# mapleCUL_small_31.net
KiCad netlist of a schematic drawn in EAGLE
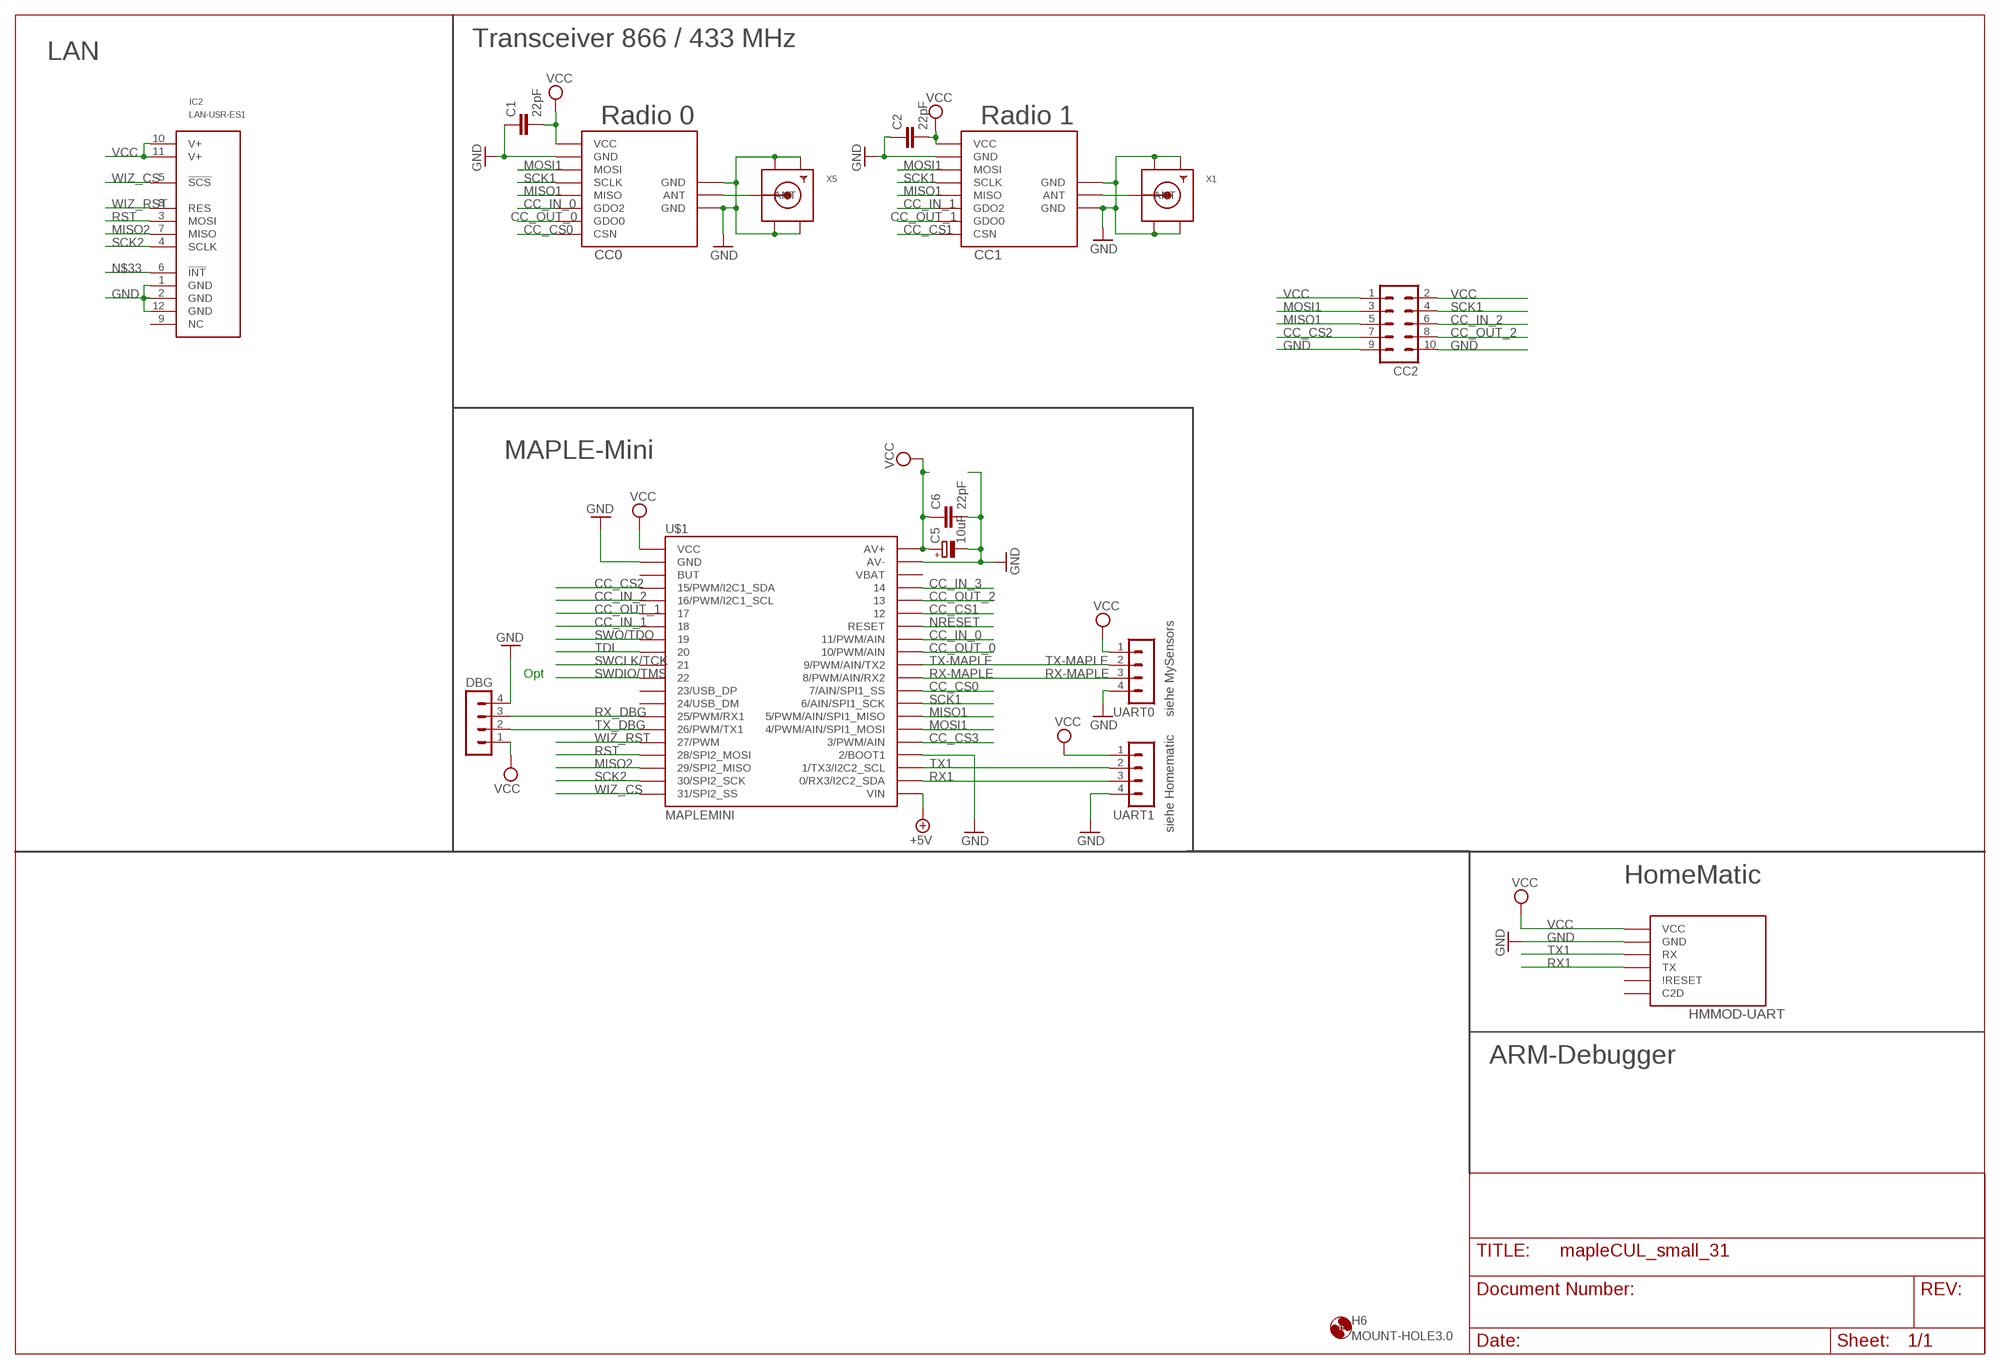
[diagram p0: schematic, sheet 1]

(export (version "E")
  (design (tool "Eeschema 10.0.6"))
  (components
    (comp (ref "C1")
      (value "22pF")
      (footprint "eagle-import:C0805")
      (libsource (lib "eagle-import") (part "C-EUC0805"))
    )
    (comp (ref "C2")
      (value "22pF")
      (footprint "eagle-import:C0805")
      (libsource (lib "eagle-import") (part "C-EUC0805"))
    )
    (comp (ref "C5")
      (value "10uF")
      (footprint "eagle-import:R_2012-12W")
      (libsource (lib "eagle-import") (part "CPOL-EUR/2012-12W"))
    )
    (comp (ref "C6")
      (value "22pF")
      (footprint "eagle-import:C0805")
      (libsource (lib "eagle-import") (part "C-EUC0805"))
    )
    (comp (ref "CC0")
      (value "CC1101")
      (footprint "eagle-import:CC1101_MODULE1_SMD")
      (libsource (lib "eagle-import") (part "CC1101_MODULE1SMD"))
    )
    (comp (ref "CC1")
      (value "CC1101_MODULE1SMD")
      (footprint "eagle-import:CC1101_MODULE1_SMD")
      (libsource (lib "eagle-import") (part "CC1101_MODULE1SMD"))
    )
    (comp (ref "CC2")
      (value "MA05-2")
      (footprint "eagle-import:MA05-2")
      (libsource (lib "eagle-import") (part "MA05-2"))
    )
    (comp (ref "DBG")
      (value "MA04-1")
      (footprint "eagle-import:MA04-1")
      (libsource (lib "eagle-import") (part "MA04-1"))
    )
    (comp (ref "H6")
      (value "MOUNT-HOLE3.0")
      (footprint "eagle-import:3,0")
      (libsource (lib "eagle-import") (part "MOUNT-HOLE3.0"))
    )
    (comp (ref "HMMOD-UART")
      (value "HM-MOD-UARTDIL")
      (footprint "eagle-import:HM-MOD-UART-DIL")
      (libsource (lib "eagle-import") (part "HM-MOD-UARTDIL"))
    )
    (comp (ref "IC2")
      (value "LAN-USR-ES1")
      (footprint "eagle-import:USR-ES1")
      (libsource (lib "eagle-import") (part "LAN-USR-ES1"))
    )
    (comp (ref "U$1")
      (value "MAPLEMINI")
      (footprint "eagle-import:20-DIP")
      (libsource (lib "eagle-import") (part "MAPLEMINI"))
    )
    (comp (ref "UART0")
      (value "MA04-1")
      (footprint "eagle-import:MA04-1")
      (libsource (lib "eagle-import") (part "MA04-1"))
    )
    (comp (ref "UART1")
      (value "MA04-1")
      (footprint "eagle-import:MA04-1")
      (libsource (lib "eagle-import") (part "MA04-1"))
    )
    (comp (ref "X1")
      (value "SMACONNECTOR_EDGE_UFL")
      (footprint "eagle-import:SMA_EDGELAUNCH_UFL")
      (libsource (lib "eagle-import") (part "SMACONNECTOR_EDGE_UFL"))
    )
    (comp (ref "X5")
      (value "SMACONNECTOR_EDGE_UFL")
      (footprint "eagle-import:SMA_EDGELAUNCH_UFL")
      (libsource (lib "eagle-import") (part "SMACONNECTOR_EDGE_UFL"))
    )
  )
  (nets
    (net (code "1") (name "+5V") (class "Default")
      (node (ref "U$1") (pin "21") (pinfunction "VIN_21") (pintype "bidirectional"))
    )
    (net (code "2") (name "/CC_CS0") (class "Default")
      (node (ref "CC0") (pin "CSN") (pinfunction "CSN_CSN") (pintype "bidirectional"))
      (node (ref "U$1") (pin "29") (pinfunction "7/AIN/SPI1_SS_29") (pintype "bidirectional"))
    )
    (net (code "3") (name "/CC_CS1") (class "Default")
      (node (ref "CC1") (pin "CSN") (pinfunction "CSN_CSN") (pintype "bidirectional"))
      (node (ref "U$1") (pin "35") (pinfunction "12_35") (pintype "bidirectional"))
    )
    (net (code "4") (name "/CC_CS2") (class "Default")
      (node (ref "CC2") (pin "7") (pinfunction "7_7") (pintype "passive"))
      (node (ref "U$1") (pin "4") (pinfunction "15/PWM/I2C1_SDA_4") (pintype "bidirectional"))
    )
    (net (code "5") (name "/CC_CS3") (class "Default")
      (node (ref "U$1") (pin "25") (pinfunction "3/PWM/AIN_25") (pintype "bidirectional"))
    )
    (net (code "6") (name "/CC_IN_0") (class "Default")
      (node (ref "CC0") (pin "GDO2") (pinfunction "GDO2_GDO2") (pintype "bidirectional"))
      (node (ref "U$1") (pin "33") (pinfunction "11/PWM/AIN_33") (pintype "bidirectional"))
    )
    (net (code "7") (name "/CC_IN_1") (class "Default")
      (node (ref "CC1") (pin "GDO2") (pinfunction "GDO2_GDO2") (pintype "bidirectional"))
      (node (ref "U$1") (pin "7") (pinfunction "18_7") (pintype "bidirectional"))
    )
    (net (code "8") (name "/CC_IN_2") (class "Default")
      (node (ref "CC2") (pin "6") (pinfunction "6_6") (pintype "passive"))
      (node (ref "U$1") (pin "5") (pinfunction "16/PWM/I2C1_SCL_5") (pintype "bidirectional"))
    )
    (net (code "9") (name "/CC_IN_3") (class "Default")
      (node (ref "U$1") (pin "37") (pinfunction "14_37") (pintype "bidirectional"))
    )
    (net (code "10") (name "/CC_OUT_0") (class "Default")
      (node (ref "CC0") (pin "GDO0") (pinfunction "GDO0_GDO0") (pintype "bidirectional"))
      (node (ref "U$1") (pin "32") (pinfunction "10/PWM/AIN_32") (pintype "bidirectional"))
    )
    (net (code "11") (name "/CC_OUT_1") (class "Default")
      (node (ref "CC1") (pin "GDO0") (pinfunction "GDO0_GDO0") (pintype "bidirectional"))
      (node (ref "U$1") (pin "6") (pinfunction "17_6") (pintype "bidirectional"))
    )
    (net (code "12") (name "/CC_OUT_2") (class "Default")
      (node (ref "CC2") (pin "8") (pinfunction "8_8") (pintype "passive"))
      (node (ref "U$1") (pin "36") (pinfunction "13_36") (pintype "bidirectional"))
    )
    (net (code "13") (name "/MISO1") (class "Default")
      (node (ref "CC0") (pin "MISO") (pinfunction "MISO_MISO") (pintype "bidirectional"))
      (node (ref "CC1") (pin "MISO") (pinfunction "MISO_MISO") (pintype "bidirectional"))
      (node (ref "CC2") (pin "5") (pinfunction "5_5") (pintype "passive"))
      (node (ref "U$1") (pin "27") (pinfunction "5/PWM/AIN/SPI1_MISO_27") (pintype "bidirectional"))
    )
    (net (code "14") (name "/MISO2") (class "Default")
      (node (ref "IC2") (pin "7") (pinfunction "MISO_7") (pintype "bidirectional"))
      (node (ref "U$1") (pin "18") (pinfunction "29/SPI2_MISO_18") (pintype "bidirectional"))
    )
    (net (code "15") (name "/MOSI1") (class "Default")
      (node (ref "CC0") (pin "MOSI") (pinfunction "MOSI_MOSI") (pintype "bidirectional"))
      (node (ref "CC1") (pin "MOSI") (pinfunction "MOSI_MOSI") (pintype "bidirectional"))
      (node (ref "CC2") (pin "3") (pinfunction "3_3") (pintype "passive"))
      (node (ref "U$1") (pin "26") (pinfunction "4/PWM/AIN/SPI1_MOSI_26") (pintype "bidirectional"))
    )
    (net (code "16") (name "/N$33") (class "Default")
      (node (ref "IC2") (pin "6") (pinfunction "~{INT}_6") (pintype "output"))
    )
    (net (code "17") (name "/NRESET") (class "Default")
      (node (ref "U$1") (pin "34") (pinfunction "RESET_34") (pintype "bidirectional"))
    )
    (net (code "18") (name "/RST") (class "Default")
      (node (ref "IC2") (pin "3") (pinfunction "MOSI_3") (pintype "bidirectional"))
      (node (ref "U$1") (pin "17") (pinfunction "28/SPI2_MOSI_17") (pintype "bidirectional"))
    )
    (net (code "19") (name "/RX-MAPLE") (class "Default")
      (node (ref "U$1") (pin "30") (pinfunction "8/PWM/AIN/RX2_30") (pintype "bidirectional"))
      (node (ref "UART0") (pin "3") (pinfunction "3_3") (pintype "passive"))
    )
    (net (code "20") (name "/RX1") (class "Default")
      (node (ref "HMMOD-UART") (pin "5") (pinfunction "TX_5") (pintype "bidirectional"))
      (node (ref "U$1") (pin "22") (pinfunction "0/RX3/I2C2_SDA_22") (pintype "bidirectional"))
      (node (ref "UART1") (pin "3") (pinfunction "3_3") (pintype "passive"))
    )
    (net (code "21") (name "/RX_DBG") (class "Default")
      (node (ref "DBG") (pin "3") (pinfunction "3_3") (pintype "passive"))
      (node (ref "U$1") (pin "14") (pinfunction "25/PWM/RX1_14") (pintype "bidirectional"))
    )
    (net (code "22") (name "/SCK1") (class "Default")
      (node (ref "CC0") (pin "SCLK") (pinfunction "SCLK_SCLK") (pintype "bidirectional"))
      (node (ref "CC1") (pin "SCLK") (pinfunction "SCLK_SCLK") (pintype "bidirectional"))
      (node (ref "CC2") (pin "4") (pinfunction "4_4") (pintype "passive"))
      (node (ref "U$1") (pin "28") (pinfunction "6/AIN/SPI1_SCK_28") (pintype "bidirectional"))
    )
    (net (code "23") (name "/SCK2") (class "Default")
      (node (ref "IC2") (pin "4") (pinfunction "SCLK_4") (pintype "input"))
      (node (ref "U$1") (pin "19") (pinfunction "30/SPI2_SCK_19") (pintype "bidirectional"))
    )
    (net (code "24") (name "/SWCLK{slash}TCK") (class "Default")
      (node (ref "U$1") (pin "10") (pinfunction "21_10") (pintype "bidirectional"))
    )
    (net (code "25") (name "/SWDIO{slash}TMS") (class "Default")
      (node (ref "U$1") (pin "11") (pinfunction "22_11") (pintype "bidirectional"))
    )
    (net (code "26") (name "/SWO{slash}TDO") (class "Default")
      (node (ref "U$1") (pin "8") (pinfunction "19_8") (pintype "bidirectional"))
    )
    (net (code "27") (name "/TDI") (class "Default")
      (node (ref "U$1") (pin "9") (pinfunction "20_9") (pintype "bidirectional"))
    )
    (net (code "28") (name "/TX-MAPLE") (class "Default")
      (node (ref "U$1") (pin "31") (pinfunction "9/PWM/AIN/TX2_31") (pintype "bidirectional"))
      (node (ref "UART0") (pin "2") (pinfunction "2_2") (pintype "passive"))
    )
    (net (code "29") (name "/TX1") (class "Default")
      (node (ref "HMMOD-UART") (pin "6") (pinfunction "RX_6") (pintype "bidirectional"))
      (node (ref "U$1") (pin "23") (pinfunction "1/TX3/I2C2_SCL_23") (pintype "bidirectional"))
      (node (ref "UART1") (pin "2") (pinfunction "2_2") (pintype "passive"))
    )
    (net (code "30") (name "/TX_DBG") (class "Default")
      (node (ref "DBG") (pin "2") (pinfunction "2_2") (pintype "passive"))
      (node (ref "U$1") (pin "15") (pinfunction "26/PWM/TX1_15") (pintype "bidirectional"))
    )
    (net (code "31") (name "/WIZ_CS") (class "Default")
      (node (ref "IC2") (pin "5") (pinfunction "~{SCS}_5") (pintype "input"))
      (node (ref "U$1") (pin "20") (pinfunction "31/SPI2_SS_20") (pintype "bidirectional"))
    )
    (net (code "32") (name "/WIZ_RST") (class "Default")
      (node (ref "IC2") (pin "8") (pinfunction "RES_8") (pintype "input"))
      (node (ref "U$1") (pin "16") (pinfunction "27/PWM_16") (pintype "bidirectional"))
    )
    (net (code "33") (name "GND") (class "Default")
      (node (ref "C1") (pin "1") (pinfunction "1_1") (pintype "passive"))
      (node (ref "C2") (pin "1") (pinfunction "1_1") (pintype "passive"))
      (node (ref "C5") (pin "-") (pinfunction "-_-") (pintype "passive"))
      (node (ref "C6") (pin "2") (pinfunction "2_2") (pintype "passive"))
      (node (ref "CC0") (pin "GND@0") (pinfunction "GND_GND@0") (pintype "power_in"))
      (node (ref "CC0") (pin "GND@1") (pinfunction "GND_GND@1") (pintype "power_in"))
      (node (ref "CC0") (pin "GND@2") (pinfunction "GND_GND@2") (pintype "power_in"))
      (node (ref "CC1") (pin "GND@0") (pinfunction "GND_GND@0") (pintype "power_in"))
      (node (ref "CC1") (pin "GND@1") (pinfunction "GND_GND@1") (pintype "power_in"))
      (node (ref "CC1") (pin "GND@2") (pinfunction "GND_GND@2") (pintype "power_in"))
      (node (ref "CC2") (pin "10") (pinfunction "10_10") (pintype "passive"))
      (node (ref "CC2") (pin "9") (pinfunction "9_9") (pintype "passive"))
      (node (ref "DBG") (pin "4") (pinfunction "4_4") (pintype "passive"))
      (node (ref "HMMOD-UART") (pin "2") (pinfunction "GND_2") (pintype "power_in"))
      (node (ref "IC2") (pin "1") (pinfunction "GND_1") (pintype "power_in"))
      (node (ref "IC2") (pin "12") (pinfunction "GND_12") (pintype "power_in"))
      (node (ref "IC2") (pin "2") (pinfunction "GND_2") (pintype "power_in"))
      (node (ref "U$1") (pin "2") (pinfunction "GND_2") (pintype "bidirectional"))
      (node (ref "U$1") (pin "24") (pinfunction "2/BOOT1_24") (pintype "bidirectional"))
      (node (ref "U$1") (pin "39") (pinfunction "AV-_39") (pintype "bidirectional"))
      (node (ref "UART0") (pin "4") (pinfunction "4_4") (pintype "passive"))
      (node (ref "UART1") (pin "4") (pinfunction "4_4") (pintype "passive"))
      (node (ref "X1") (pin "GND@1") (pinfunction "GND1_GND@1") (pintype "power_in"))
      (node (ref "X1") (pin "GND@2") (pinfunction "GND2_GND@2") (pintype "power_in"))
      (node (ref "X1") (pin "GND@3") (pinfunction "GND3_GND@3") (pintype "power_in"))
      (node (ref "X1") (pin "GND@4") (pinfunction "GND4_GND@4") (pintype "power_in"))
      (node (ref "X5") (pin "GND@1") (pinfunction "GND1_GND@1") (pintype "power_in"))
      (node (ref "X5") (pin "GND@2") (pinfunction "GND2_GND@2") (pintype "power_in"))
      (node (ref "X5") (pin "GND@3") (pinfunction "GND3_GND@3") (pintype "power_in"))
      (node (ref "X5") (pin "GND@4") (pinfunction "GND4_GND@4") (pintype "power_in"))
    )
    (net (code "34") (name "Net-(X1-ANT)") (class "Default")
      (node (ref "CC1") (pin "ANT") (pinfunction "ANT_ANT") (pintype "output"))
      (node (ref "X1") (pin "P") (pinfunction "ANT_P") (pintype "bidirectional"))
    )
    (net (code "35") (name "Net-(X5-ANT)") (class "Default")
      (node (ref "CC0") (pin "ANT") (pinfunction "ANT_ANT") (pintype "output"))
      (node (ref "X5") (pin "P") (pinfunction "ANT_P") (pintype "bidirectional"))
    )
    (net (code "36") (name "VCC") (class "Default")
      (node (ref "C1") (pin "2") (pinfunction "2_2") (pintype "passive"))
      (node (ref "C2") (pin "2") (pinfunction "2_2") (pintype "passive"))
      (node (ref "C5") (pin "+") (pinfunction "+_+") (pintype "passive"))
      (node (ref "C6") (pin "1") (pinfunction "1_1") (pintype "passive"))
      (node (ref "CC0") (pin "VCC") (pinfunction "VCC_VCC") (pintype "power_in"))
      (node (ref "CC1") (pin "VCC") (pinfunction "VCC_VCC") (pintype "power_in"))
      (node (ref "CC2") (pin "1") (pinfunction "1_1") (pintype "passive"))
      (node (ref "CC2") (pin "2") (pinfunction "2_2") (pintype "passive"))
      (node (ref "DBG") (pin "1") (pinfunction "1_1") (pintype "passive"))
      (node (ref "HMMOD-UART") (pin "1") (pinfunction "VCC_1") (pintype "power_in"))
      (node (ref "IC2") (pin "10") (pinfunction "V+_10") (pintype "power_in"))
      (node (ref "IC2") (pin "11") (pinfunction "V+_11") (pintype "power_in"))
      (node (ref "U$1") (pin "1") (pinfunction "VCC_1") (pintype "bidirectional"))
      (node (ref "U$1") (pin "40") (pinfunction "AV+_40") (pintype "bidirectional"))
      (node (ref "UART0") (pin "1") (pinfunction "1_1") (pintype "passive"))
      (node (ref "UART1") (pin "1") (pinfunction "1_1") (pintype "passive"))
    )
    (net (code "37") (name "unconnected-(HMMOD-UART-C2D-Pad3)") (class "Default")
      (node (ref "HMMOD-UART") (pin "3") (pinfunction "C2D_3") (pintype "bidirectional"))
    )
    (net (code "38") (name "unconnected-(HMMOD-UART-\\~{RESET}-Pad4)") (class "Default")
      (node (ref "HMMOD-UART") (pin "4") (pinfunction "\\~{RESET}_4") (pintype "bidirectional"))
    )
    (net (code "39") (name "unconnected-(IC2-NC-Pad9)") (class "Default")
      (node (ref "IC2") (pin "9") (pinfunction "NC_9") (pintype "no_connect"))
    )
    (net (code "40") (name "unconnected-(U$1-23{slash}USB_DP-Pad12)") (class "Default")
      (node (ref "U$1") (pin "12") (pinfunction "23/USB_DP_12") (pintype "bidirectional"))
    )
    (net (code "41") (name "unconnected-(U$1-24{slash}USB_DM-Pad13)") (class "Default")
      (node (ref "U$1") (pin "13") (pinfunction "24/USB_DM_13") (pintype "bidirectional"))
    )
    (net (code "42") (name "unconnected-(U$1-BUT-Pad3)") (class "Default")
      (node (ref "U$1") (pin "3") (pinfunction "BUT_3") (pintype "bidirectional"))
    )
    (net (code "43") (name "unconnected-(U$1-VBAT-Pad38)") (class "Default")
      (node (ref "U$1") (pin "38") (pinfunction "VBAT_38") (pintype "bidirectional"))
    )
  )
)
